# ftdi-485.net
KiCad netlist of a schematic drawn in EAGLE
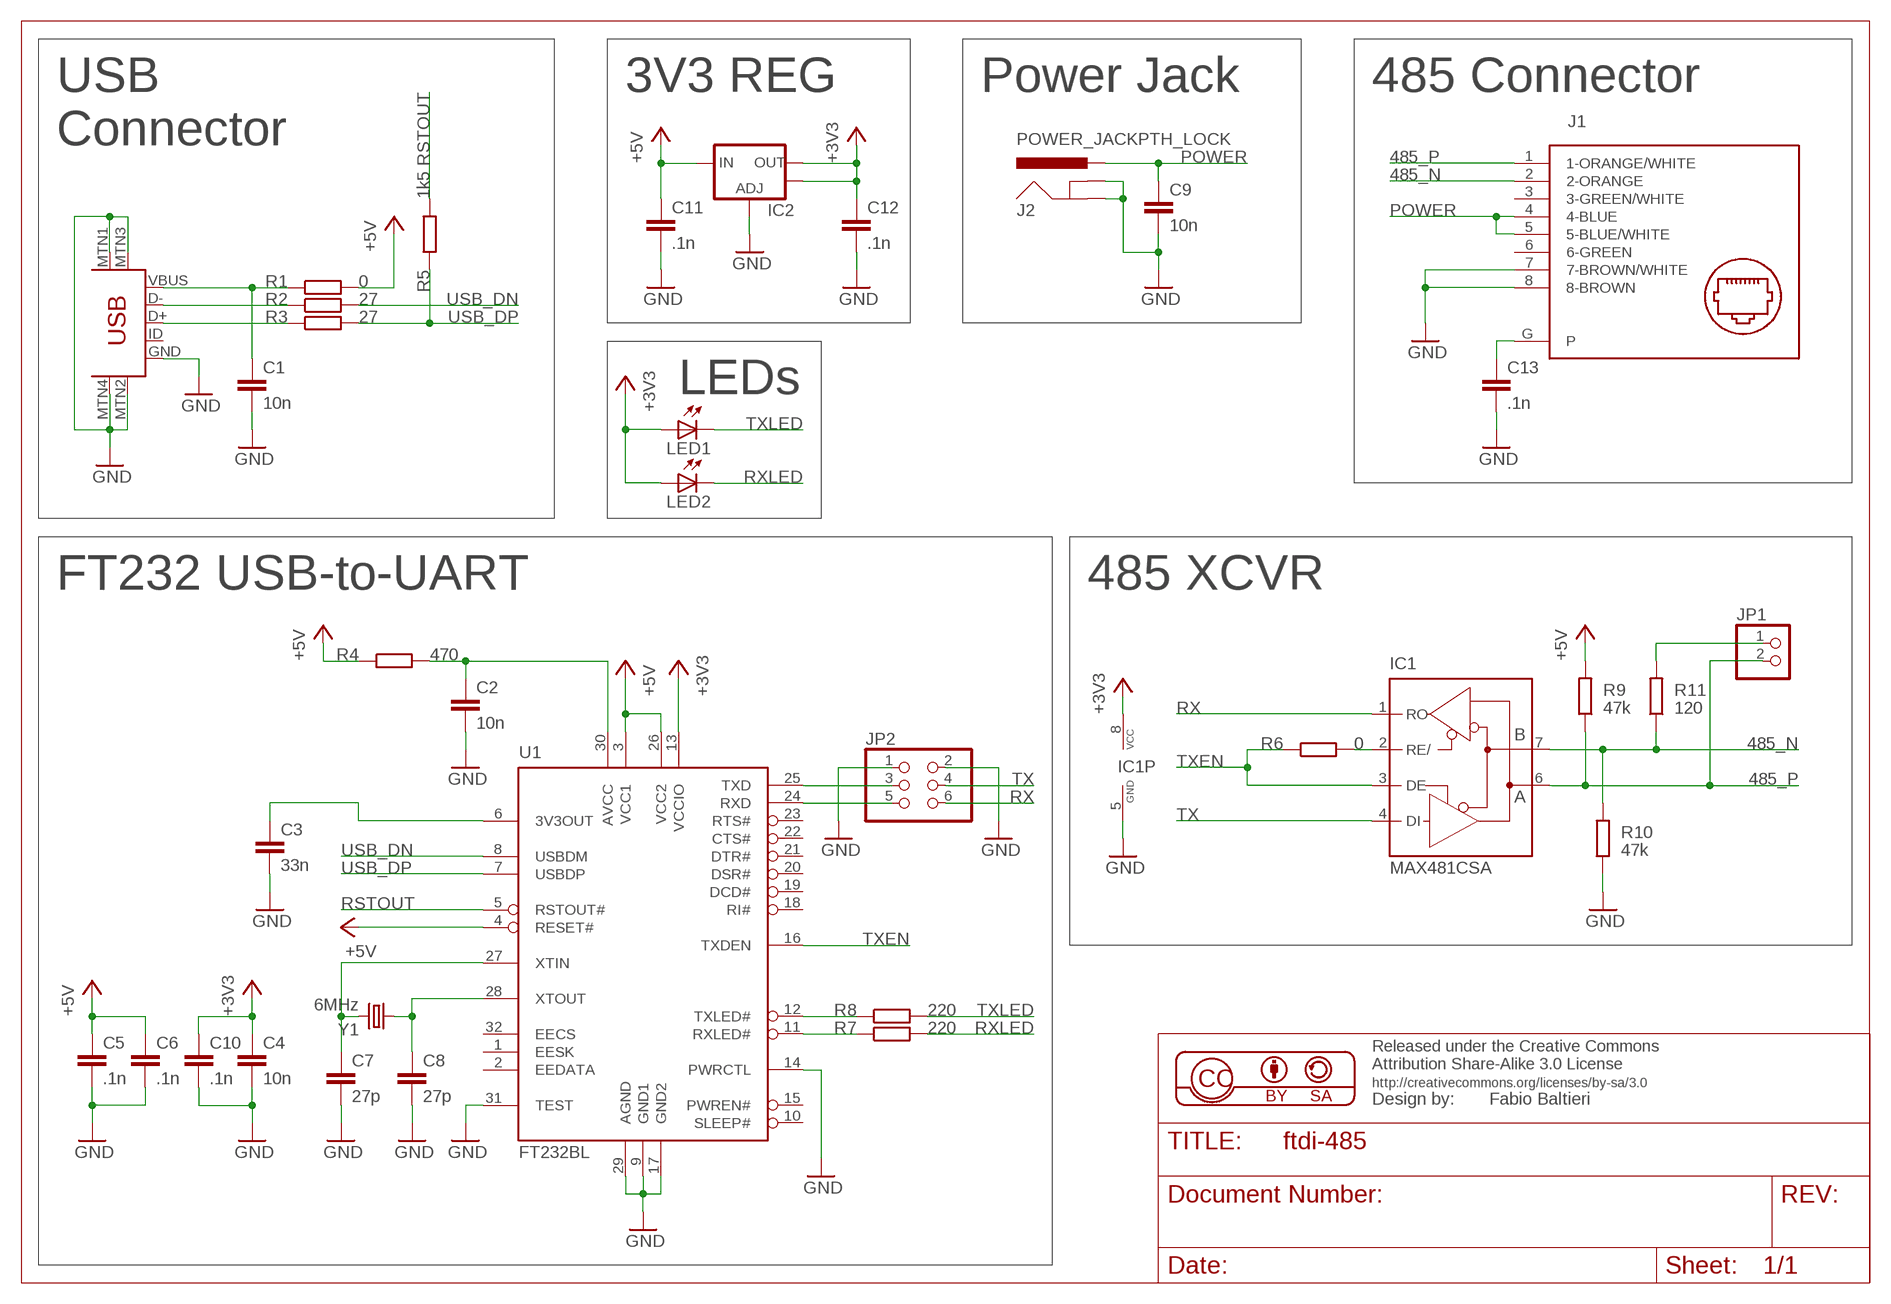
[diagram p0: schematic, sheet 1]

(export (version "E")
  (design (tool "Eeschema 10.0.6"))
  (components
    (comp (ref "C1")
      (value "10n")
      (footprint "eagle-import:C0805")
      (libsource (lib "eagle-import") (part "C-EUC0805"))
    )
    (comp (ref "C2")
      (value "10n")
      (footprint "eagle-import:C0805")
      (libsource (lib "eagle-import") (part "C-EUC0805"))
    )
    (comp (ref "C3")
      (value "33n")
      (footprint "eagle-import:C0805")
      (libsource (lib "eagle-import") (part "C-EUC0805"))
    )
    (comp (ref "C4")
      (value "10n")
      (footprint "eagle-import:C0805")
      (libsource (lib "eagle-import") (part "C-EUC0805"))
    )
    (comp (ref "C5")
      (value ".1n")
      (footprint "eagle-import:C0805")
      (libsource (lib "eagle-import") (part "C-EUC0805"))
    )
    (comp (ref "C6")
      (value ".1n")
      (footprint "eagle-import:C0805")
      (libsource (lib "eagle-import") (part "C-EUC0805"))
    )
    (comp (ref "C7")
      (value "27p")
      (footprint "eagle-import:C0805")
      (libsource (lib "eagle-import") (part "C-EUC0805"))
    )
    (comp (ref "C8")
      (value "27p")
      (footprint "eagle-import:C0805")
      (libsource (lib "eagle-import") (part "C-EUC0805"))
    )
    (comp (ref "C9")
      (value "10n")
      (footprint "eagle-import:C0805")
      (libsource (lib "eagle-import") (part "C-EUC0805"))
    )
    (comp (ref "C10")
      (value ".1n")
      (footprint "eagle-import:C0805")
      (libsource (lib "eagle-import") (part "C-EUC0805"))
    )
    (comp (ref "C11")
      (value ".1n")
      (footprint "eagle-import:C0805")
      (libsource (lib "eagle-import") (part "C-EUC0805"))
    )
    (comp (ref "C12")
      (value ".1n")
      (footprint "eagle-import:C0805")
      (libsource (lib "eagle-import") (part "C-EUC0805"))
    )
    (comp (ref "C13")
      (value ".1n")
      (footprint "eagle-import:C0805")
      (libsource (lib "eagle-import") (part "C-EUC0805"))
    )
    (comp (ref "IC1")
      (value "MAX481CSA")
      (footprint "eagle-import:SO08")
      (libsource (lib "eagle-import") (part "MAX481CSA"))
    )
    (comp (ref "IC2")
      (value "V_REG_LM1117SOT223")
      (footprint "eagle-import:SOT223")
      (libsource (lib "eagle-import") (part "V_REG_LM1117SOT223"))
    )
    (comp (ref "J1")
      (value "NE8FAH")
      (footprint "eagle-import:NE8FAH")
      (libsource (lib "eagle-import") (part "NE8FAH"))
    )
    (comp (ref "J2")
      (value "POWER_JACKPTH_LOCK")
      (footprint "eagle-import:POWER_JACK_PTH_LOCK")
      (libsource (lib "eagle-import") (part "POWER_JACKPTH_LOCK"))
    )
    (comp (ref "JP1")
      (value "PINHD-1X2")
      (footprint "eagle-import:1X02")
      (libsource (lib "eagle-import") (part "PINHD-1X2"))
    )
    (comp (ref "JP2")
      (value "PINHD-2X3")
      (footprint "eagle-import:2X03")
      (libsource (lib "eagle-import") (part "PINHD-2X3"))
    )
    (comp (ref "LED1")
      (value "LEDCHIP-LED0805")
      (footprint "eagle-import:CHIP-LED0805")
      (libsource (lib "eagle-import") (part "LEDCHIP-LED0805"))
    )
    (comp (ref "LED2")
      (value "LEDCHIP-LED0805")
      (footprint "eagle-import:CHIP-LED0805")
      (libsource (lib "eagle-import") (part "LEDCHIP-LED0805"))
    )
    (comp (ref "R1")
      (value "0")
      (footprint "eagle-import:R0603")
      (libsource (lib "eagle-import") (part "R-EU_R0603"))
    )
    (comp (ref "R2")
      (value "27")
      (footprint "eagle-import:R0603")
      (libsource (lib "eagle-import") (part "R-EU_R0603"))
    )
    (comp (ref "R3")
      (value "27")
      (footprint "eagle-import:R0603")
      (libsource (lib "eagle-import") (part "R-EU_R0603"))
    )
    (comp (ref "R4")
      (value "470")
      (footprint "eagle-import:R0603")
      (libsource (lib "eagle-import") (part "R-EU_R0603"))
    )
    (comp (ref "R5")
      (value "1k5")
      (footprint "eagle-import:R0603")
      (libsource (lib "eagle-import") (part "R-EU_R0603"))
    )
    (comp (ref "R6")
      (value "0")
      (footprint "eagle-import:R0603")
      (libsource (lib "eagle-import") (part "R-EU_R0603"))
    )
    (comp (ref "R7")
      (value "220")
      (footprint "eagle-import:R0603")
      (libsource (lib "eagle-import") (part "R-EU_R0603"))
    )
    (comp (ref "R8")
      (value "220")
      (footprint "eagle-import:R0603")
      (libsource (lib "eagle-import") (part "R-EU_R0603"))
    )
    (comp (ref "R9")
      (value "47k")
      (footprint "eagle-import:R0603")
      (libsource (lib "eagle-import") (part "R-EU_R0603"))
    )
    (comp (ref "R10")
      (value "47k")
      (footprint "eagle-import:R0603")
      (libsource (lib "eagle-import") (part "R-EU_R0603"))
    )
    (comp (ref "R11")
      (value "120")
      (footprint "eagle-import:R0603")
      (libsource (lib "eagle-import") (part "R-EU_R0603"))
    )
    (comp (ref "U$2")
      (value "USB-MINIB-5PIN")
      (footprint "eagle-import:USB-MINIB")
      (libsource (lib "eagle-import") (part "USB-MINIB-5PIN"))
    )
    (comp (ref "U1")
      (value "FT232BL")
      (footprint "eagle-import:LQFP32")
      (libsource (lib "eagle-import") (part "FT232BL"))
    )
    (comp (ref "Y1")
      (value "6MHz")
      (footprint "eagle-import:HC49U-V")
      (libsource (lib "eagle-import") (part "CRYSTALHC49UV"))
    )
  )
  (nets
    (net (code "1") (name "+3V3") (class "Default")
      (node (ref "C10") (pin "1") (pinfunction "1_1") (pintype "passive"))
      (node (ref "C12") (pin "1") (pinfunction "1_1") (pintype "passive"))
      (node (ref "C4") (pin "1") (pinfunction "1_1") (pintype "passive"))
      (node (ref "IC1") (pin "8") (pinfunction "VCC_8") (pintype "power_in"))
      (node (ref "IC2") (pin "2") (pinfunction "OUT_2") (pintype "output"))
      (node (ref "IC2") (pin "4") (pinfunction "OUT_4") (pintype "output"))
      (node (ref "LED1") (pin "A") (pinfunction "A_A") (pintype "passive"))
      (node (ref "LED2") (pin "A") (pinfunction "A_A") (pintype "passive"))
      (node (ref "U1") (pin "13") (pinfunction "VCCIO_13") (pintype "power_in"))
    )
    (net (code "2") (name "+5V") (class "Default")
      (node (ref "C11") (pin "1") (pinfunction "1_1") (pintype "passive"))
      (node (ref "C5") (pin "1") (pinfunction "1_1") (pintype "passive"))
      (node (ref "C6") (pin "1") (pinfunction "1_1") (pintype "passive"))
      (node (ref "IC2") (pin "3") (pinfunction "IN_3") (pintype "input"))
      (node (ref "R1") (pin "2") (pinfunction "2_2") (pintype "passive"))
      (node (ref "R4") (pin "1") (pinfunction "1_1") (pintype "passive"))
      (node (ref "R9") (pin "2") (pinfunction "2_2") (pintype "passive"))
      (node (ref "U1") (pin "26") (pinfunction "VCC2_26") (pintype "power_in"))
      (node (ref "U1") (pin "3") (pinfunction "VCC1_3") (pintype "power_in"))
      (node (ref "U1") (pin "4") (pinfunction "RESET#_4") (pintype "input"))
    )
    (net (code "3") (name "/485_N") (class "Default")
      (node (ref "IC1") (pin "7") (pinfunction "B_7") (pintype "passive"))
      (node (ref "J1") (pin "2") (pinfunction "2-ORANGE_2") (pintype "bidirectional"))
      (node (ref "R10") (pin "2") (pinfunction "2_2") (pintype "passive"))
      (node (ref "R11") (pin "1") (pinfunction "1_1") (pintype "passive"))
    )
    (net (code "4") (name "/485_P") (class "Default")
      (node (ref "IC1") (pin "6") (pinfunction "A_6") (pintype "passive"))
      (node (ref "J1") (pin "1") (pinfunction "1-ORANGE/WHITE_1") (pintype "bidirectional"))
      (node (ref "JP1") (pin "2") (pinfunction "2_2") (pintype "passive"))
      (node (ref "R9") (pin "1") (pinfunction "1_1") (pintype "passive"))
    )
    (net (code "5") (name "/POWER") (class "Default")
      (node (ref "C9") (pin "1") (pinfunction "1_1") (pintype "passive"))
      (node (ref "J1") (pin "4") (pinfunction "4-BLUE_4") (pintype "bidirectional"))
      (node (ref "J1") (pin "5") (pinfunction "5-BLUE/WHITE_5") (pintype "bidirectional"))
      (node (ref "J2") (pin "PWR") (pinfunction "PWR_PWR") (pintype "bidirectional"))
    )
    (net (code "6") (name "/RSTOUT") (class "Default")
      (node (ref "R5") (pin "2") (pinfunction "2_2") (pintype "passive"))
      (node (ref "U1") (pin "5") (pinfunction "RSTOUT#_5") (pintype "output"))
    )
    (net (code "7") (name "/RX") (class "Default")
      (node (ref "IC1") (pin "1") (pinfunction "RO_1") (pintype "output"))
      (node (ref "JP2") (pin "6") (pinfunction "6_6") (pintype "passive"))
    )
    (net (code "8") (name "/RXLED") (class "Default")
      (node (ref "LED2") (pin "C") (pinfunction "C_C") (pintype "passive"))
      (node (ref "R7") (pin "2") (pinfunction "2_2") (pintype "passive"))
    )
    (net (code "9") (name "/TX") (class "Default")
      (node (ref "IC1") (pin "4") (pinfunction "DI_4") (pintype "input"))
      (node (ref "JP2") (pin "4") (pinfunction "4_4") (pintype "passive"))
    )
    (net (code "10") (name "/TXEN") (class "Default")
      (node (ref "IC1") (pin "3") (pinfunction "DE_3") (pintype "input"))
      (node (ref "R6") (pin "1") (pinfunction "1_1") (pintype "passive"))
      (node (ref "U1") (pin "16") (pinfunction "TXDEN_16") (pintype "output"))
    )
    (net (code "11") (name "/TXLED") (class "Default")
      (node (ref "LED1") (pin "C") (pinfunction "C_C") (pintype "passive"))
      (node (ref "R8") (pin "2") (pinfunction "2_2") (pintype "passive"))
    )
    (net (code "12") (name "/USB_DN") (class "Default")
      (node (ref "R2") (pin "2") (pinfunction "2_2") (pintype "passive"))
      (node (ref "U1") (pin "8") (pinfunction "USBDM_8") (pintype "bidirectional"))
    )
    (net (code "13") (name "/USB_DP") (class "Default")
      (node (ref "R3") (pin "2") (pinfunction "2_2") (pintype "passive"))
      (node (ref "R5") (pin "1") (pinfunction "1_1") (pintype "passive"))
      (node (ref "U1") (pin "7") (pinfunction "USBDP_7") (pintype "bidirectional"))
    )
    (net (code "14") (name "GND") (class "Default")
      (node (ref "C1") (pin "2") (pinfunction "2_2") (pintype "passive"))
      (node (ref "C10") (pin "2") (pinfunction "2_2") (pintype "passive"))
      (node (ref "C11") (pin "2") (pinfunction "2_2") (pintype "passive"))
      (node (ref "C12") (pin "2") (pinfunction "2_2") (pintype "passive"))
      (node (ref "C13") (pin "2") (pinfunction "2_2") (pintype "passive"))
      (node (ref "C2") (pin "2") (pinfunction "2_2") (pintype "passive"))
      (node (ref "C3") (pin "2") (pinfunction "2_2") (pintype "passive"))
      (node (ref "C4") (pin "2") (pinfunction "2_2") (pintype "passive"))
      (node (ref "C5") (pin "2") (pinfunction "2_2") (pintype "passive"))
      (node (ref "C6") (pin "2") (pinfunction "2_2") (pintype "passive"))
      (node (ref "C7") (pin "2") (pinfunction "2_2") (pintype "passive"))
      (node (ref "C8") (pin "2") (pinfunction "2_2") (pintype "passive"))
      (node (ref "C9") (pin "2") (pinfunction "2_2") (pintype "passive"))
      (node (ref "IC1") (pin "5") (pinfunction "GND_5") (pintype "power_in"))
      (node (ref "IC2") (pin "1") (pinfunction "ADJ_1") (pintype "input"))
      (node (ref "J1") (pin "7") (pinfunction "7-BROWN/WHITE_7") (pintype "bidirectional"))
      (node (ref "J1") (pin "8") (pinfunction "8-BROWN_8") (pintype "bidirectional"))
      (node (ref "J2") (pin "GND") (pinfunction "GND_GND") (pintype "bidirectional"))
      (node (ref "J2") (pin "GNDBREAK") (pinfunction "GNDBREAK_GNDBREAK") (pintype "bidirectional"))
      (node (ref "JP2") (pin "1") (pinfunction "1_1") (pintype "passive"))
      (node (ref "JP2") (pin "2") (pinfunction "2_2") (pintype "passive"))
      (node (ref "R10") (pin "1") (pinfunction "1_1") (pintype "passive"))
      (node (ref "U$2") (pin "GND") (pinfunction "GND_GND") (pintype "bidirectional"))
      (node (ref "U$2") (pin "MTN1") (pinfunction "MTN2_MTN1") (pintype "bidirectional"))
      (node (ref "U$2") (pin "MTN2") (pinfunction "MTN3_MTN2") (pintype "bidirectional"))
      (node (ref "U$2") (pin "MTN3") (pinfunction "MTN1_MTN3") (pintype "bidirectional"))
      (node (ref "U$2") (pin "MTN4") (pinfunction "MTN4_MTN4") (pintype "bidirectional"))
      (node (ref "U1") (pin "14") (pinfunction "PWRCTL_14") (pintype "input"))
      (node (ref "U1") (pin "17") (pinfunction "GND2_17") (pintype "power_in"))
      (node (ref "U1") (pin "29") (pinfunction "AGND_29") (pintype "power_in"))
      (node (ref "U1") (pin "31") (pinfunction "TEST_31") (pintype "input"))
      (node (ref "U1") (pin "9") (pinfunction "GND1_9") (pintype "power_in"))
    )
    (net (code "15") (name "Net-(C1-Pad1)") (class "Default")
      (node (ref "C1") (pin "1") (pinfunction "1_1") (pintype "passive"))
      (node (ref "R1") (pin "1") (pinfunction "1_1") (pintype "passive"))
      (node (ref "U$2") (pin "VBUS") (pinfunction "VBUS_VBUS") (pintype "bidirectional"))
    )
    (net (code "16") (name "Net-(IC1A-RE{slash})") (class "Default")
      (node (ref "IC1") (pin "2") (pinfunction "RE/_2") (pintype "input"))
      (node (ref "R6") (pin "2") (pinfunction "2_2") (pintype "passive"))
    )
    (net (code "17") (name "Net-(J1-P)") (class "Default")
      (node (ref "C13") (pin "1") (pinfunction "1_1") (pintype "passive"))
      (node (ref "J1") (pin "G") (pinfunction "P_G") (pintype "bidirectional"))
    )
    (net (code "18") (name "Net-(JP1-Pad1)") (class "Default")
      (node (ref "JP1") (pin "1") (pinfunction "1_1") (pintype "passive"))
      (node (ref "R11") (pin "2") (pinfunction "2_2") (pintype "passive"))
    )
    (net (code "19") (name "Net-(R2-Pad1)") (class "Default")
      (node (ref "R2") (pin "1") (pinfunction "1_1") (pintype "passive"))
      (node (ref "U$2") (pin "D-") (pinfunction "D-_D-") (pintype "bidirectional"))
    )
    (net (code "20") (name "Net-(R3-Pad1)") (class "Default")
      (node (ref "R3") (pin "1") (pinfunction "1_1") (pintype "passive"))
      (node (ref "U$2") (pin "D+") (pinfunction "D+_D+") (pintype "bidirectional"))
    )
    (net (code "21") (name "Net-(U1-3V3OUT)") (class "Default")
      (node (ref "C3") (pin "1") (pinfunction "1_1") (pintype "passive"))
      (node (ref "U1") (pin "6") (pinfunction "3V3OUT_6") (pintype "output"))
    )
    (net (code "22") (name "Net-(U1-AVCC)") (class "Default")
      (node (ref "C2") (pin "1") (pinfunction "1_1") (pintype "passive"))
      (node (ref "R4") (pin "2") (pinfunction "2_2") (pintype "passive"))
      (node (ref "U1") (pin "30") (pinfunction "AVCC_30") (pintype "power_in"))
    )
    (net (code "23") (name "Net-(U1-RXD)") (class "Default")
      (node (ref "JP2") (pin "5") (pinfunction "5_5") (pintype "passive"))
      (node (ref "U1") (pin "24") (pinfunction "RXD_24") (pintype "input"))
    )
    (net (code "24") (name "Net-(U1-RXLED#)") (class "Default")
      (node (ref "R7") (pin "1") (pinfunction "1_1") (pintype "passive"))
      (node (ref "U1") (pin "11") (pinfunction "RXLED#_11") (pintype "open_collector"))
    )
    (net (code "25") (name "Net-(U1-TXD)") (class "Default")
      (node (ref "JP2") (pin "3") (pinfunction "3_3") (pintype "passive"))
      (node (ref "U1") (pin "25") (pinfunction "TXD_25") (pintype "output"))
    )
    (net (code "26") (name "Net-(U1-TXLED#)") (class "Default")
      (node (ref "R8") (pin "1") (pinfunction "1_1") (pintype "passive"))
      (node (ref "U1") (pin "12") (pinfunction "TXLED#_12") (pintype "open_collector"))
    )
    (net (code "27") (name "Net-(U1-XTIN)") (class "Default")
      (node (ref "C7") (pin "1") (pinfunction "1_1") (pintype "passive"))
      (node (ref "U1") (pin "27") (pinfunction "XTIN_27") (pintype "input"))
      (node (ref "Y1") (pin "2") (pinfunction "2_2") (pintype "passive"))
    )
    (net (code "28") (name "Net-(U1-XTOUT)") (class "Default")
      (node (ref "C8") (pin "1") (pinfunction "1_1") (pintype "passive"))
      (node (ref "U1") (pin "28") (pinfunction "XTOUT_28") (pintype "output"))
      (node (ref "Y1") (pin "1") (pinfunction "1_1") (pintype "passive"))
    )
    (net (code "29") (name "unconnected-(J1-3-GREEN{slash}WHITE-Pad3)") (class "Default")
      (node (ref "J1") (pin "3") (pinfunction "3-GREEN/WHITE_3") (pintype "bidirectional"))
    )
    (net (code "30") (name "unconnected-(J1-6-GREEN-Pad6)") (class "Default")
      (node (ref "J1") (pin "6") (pinfunction "6-GREEN_6") (pintype "bidirectional"))
    )
    (net (code "31") (name "unconnected-(U$2-PadID)") (class "Default")
      (node (ref "U$2") (pin "ID") (pinfunction "ID_ID") (pintype "bidirectional"))
    )
    (net (code "32") (name "unconnected-(U1-CTS#-Pad22)") (class "Default")
      (node (ref "U1") (pin "22") (pinfunction "CTS#_22") (pintype "input"))
    )
    (net (code "33") (name "unconnected-(U1-DCD#-Pad19)") (class "Default")
      (node (ref "U1") (pin "19") (pinfunction "DCD#_19") (pintype "input"))
    )
    (net (code "34") (name "unconnected-(U1-DSR#-Pad20)") (class "Default")
      (node (ref "U1") (pin "20") (pinfunction "DSR#_20") (pintype "input"))
    )
    (net (code "35") (name "unconnected-(U1-DTR#-Pad21)") (class "Default")
      (node (ref "U1") (pin "21") (pinfunction "DTR#_21") (pintype "output"))
    )
    (net (code "36") (name "unconnected-(U1-EECS-Pad32)") (class "Default")
      (node (ref "U1") (pin "32") (pinfunction "EECS_32") (pintype "bidirectional"))
    )
    (net (code "37") (name "unconnected-(U1-EEDATA-Pad2)") (class "Default")
      (node (ref "U1") (pin "2") (pinfunction "EEDATA_2") (pintype "bidirectional"))
    )
    (net (code "38") (name "unconnected-(U1-EESK-Pad1)") (class "Default")
      (node (ref "U1") (pin "1") (pinfunction "EESK_1") (pintype "output"))
    )
    (net (code "39") (name "unconnected-(U1-PWREN#-Pad15)") (class "Default")
      (node (ref "U1") (pin "15") (pinfunction "PWREN#_15") (pintype "output"))
    )
    (net (code "40") (name "unconnected-(U1-RI#-Pad18)") (class "Default")
      (node (ref "U1") (pin "18") (pinfunction "RI#_18") (pintype "input"))
    )
    (net (code "41") (name "unconnected-(U1-RTS#-Pad23)") (class "Default")
      (node (ref "U1") (pin "23") (pinfunction "RTS#_23") (pintype "output"))
    )
    (net (code "42") (name "unconnected-(U1-SLEEP#-Pad10)") (class "Default")
      (node (ref "U1") (pin "10") (pinfunction "SLEEP#_10") (pintype "output"))
    )
  )
)
